# CONNECTORS.net
KiCad netlist of a schematic drawn in Altium Designer
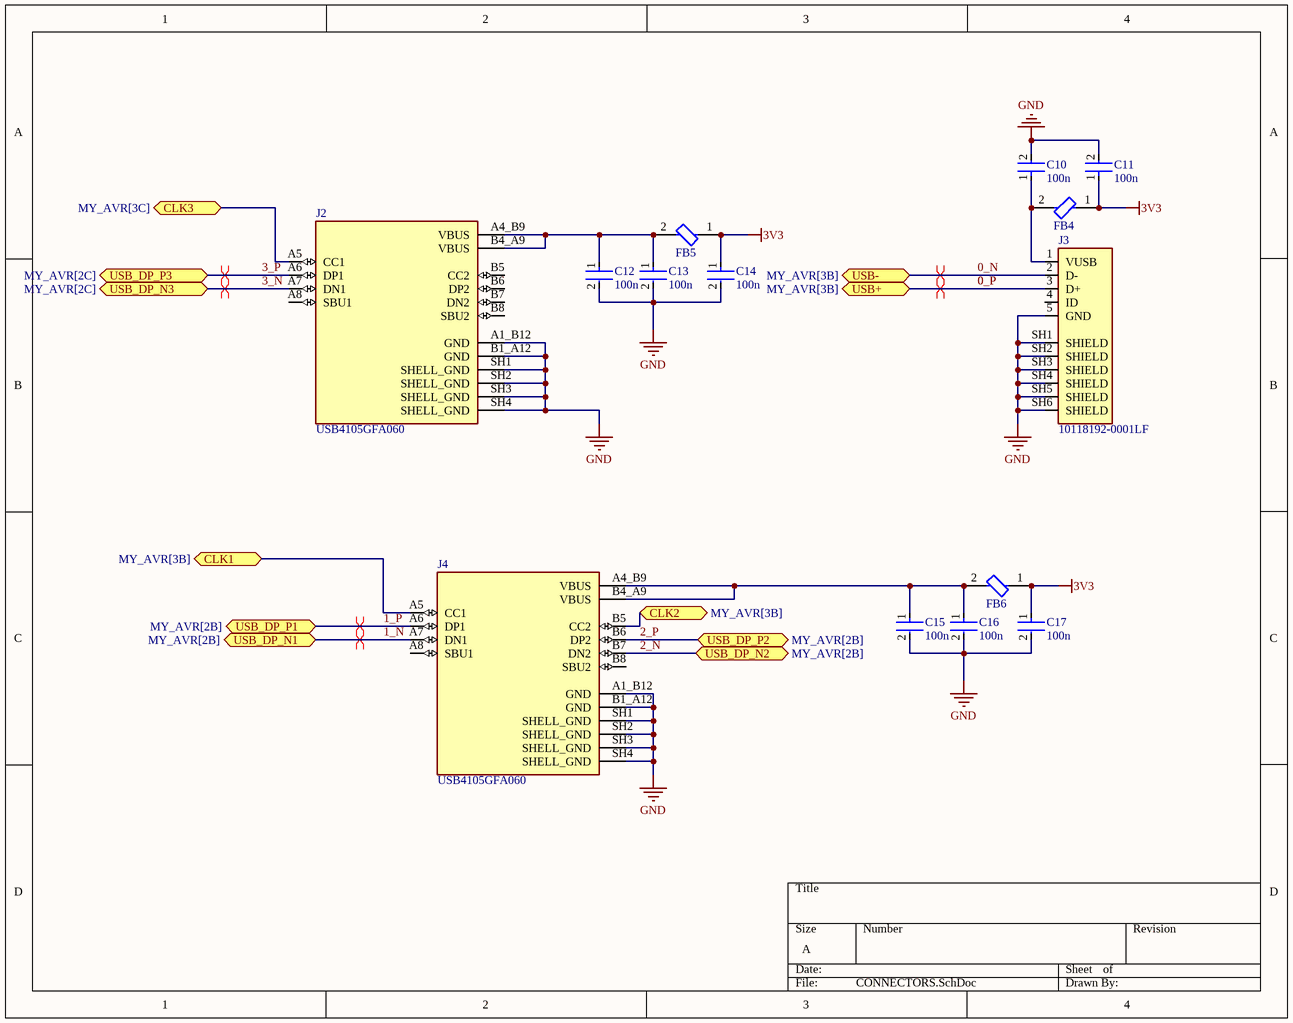
[diagram p0: CONNECTORS.SchDoc]

(export (version "E")
  (design (tool "Eeschema 10.0.6"))
  (components
    (comp (ref "C10")
      (value "100n")
      (footprint "FP-CL10-IPC_C")
      (description "Cap Ceramic 4.7uF 10V X5R ±10% Pad SMD 0603 +85°C T/R")
      (fields (field (name "TOLERANCE") "10%"))
      (libsource (lib "Altium Content Vault") (part "b4654b650e69147ec39a6b967a45e02"))
    )
    (comp (ref "C11")
      (value "100n")
      (footprint "FP-CL10-IPC_C")
      (description "Cap Ceramic 4.7uF 10V X5R ±10% Pad SMD 0603 +85°C T/R")
      (fields (field (name "TOLERANCE") "10%"))
      (libsource (lib "Altium Content Vault") (part "b4654b650e69147ec39a6b967a45e02"))
    )
    (comp (ref "C12")
      (value "100n")
      (footprint "FP-CL10-IPC_C")
      (description "Cap Ceramic 4.7uF 10V X5R ±10% Pad SMD 0603 +85°C T/R")
      (fields (field (name "TOLERANCE") "10%"))
      (libsource (lib "Altium Content Vault") (part "b4654b650e69147ec39a6b967a45e02"))
    )
    (comp (ref "C13")
      (value "100n")
      (footprint "FP-CL10-IPC_C")
      (description "Cap Ceramic 4.7uF 10V X5R ±10% Pad SMD 0603 +85°C T/R")
      (fields (field (name "TOLERANCE") "10%"))
      (libsource (lib "Altium Content Vault") (part "b4654b650e69147ec39a6b967a45e02"))
    )
    (comp (ref "C14")
      (value "100n")
      (footprint "FP-CL10-IPC_C")
      (description "Cap Ceramic 4.7uF 10V X5R ±10% Pad SMD 0603 +85°C T/R")
      (fields (field (name "TOLERANCE") "10%"))
      (libsource (lib "Altium Content Vault") (part "b4654b650e69147ec39a6b967a45e02"))
    )
    (comp (ref "C15")
      (value "100n")
      (footprint "FP-CL10-IPC_C")
      (description "Cap Ceramic 4.7uF 10V X5R ±10% Pad SMD 0603 +85°C T/R")
      (fields (field (name "TOLERANCE") "10%"))
      (libsource (lib "Altium Content Vault") (part "b4654b650e69147ec39a6b967a45e02"))
    )
    (comp (ref "C16")
      (value "100n")
      (footprint "FP-CL10-IPC_C")
      (description "Cap Ceramic 4.7uF 10V X5R ±10% Pad SMD 0603 +85°C T/R")
      (fields (field (name "TOLERANCE") "10%"))
      (libsource (lib "Altium Content Vault") (part "b4654b650e69147ec39a6b967a45e02"))
    )
    (comp (ref "C17")
      (value "100n")
      (footprint "FP-CL10-IPC_C")
      (description "Cap Ceramic 4.7uF 10V X5R ±10% Pad SMD 0603 +85°C T/R")
      (fields (field (name "TOLERANCE") "10%"))
      (libsource (lib "Altium Content Vault") (part "b4654b650e69147ec39a6b967a45e02"))
    )
    (comp (ref "FB4")
      (value "BLM18KG121TN1D")
      (footprint "FP-BLM18-0_15-t0_6-d1_2-IPC_A")
      (description "FERRITE BEAD 120 OHM 0603 1LN")
      (fields (field (name "TOLERANCE") "25%"))
      (libsource (lib "Altium Content Vault") (part "5f30dd21d616792df468990f7003faa"))
    )
    (comp (ref "FB5")
      (value "BLM18KG121TN1D")
      (footprint "FP-BLM18-0_15-t0_6-d1_2-IPC_A")
      (description "FERRITE BEAD 120 OHM 0603 1LN")
      (fields (field (name "TOLERANCE") "25%"))
      (libsource (lib "Altium Content Vault") (part "5f30dd21d616792df468990f7003faa"))
    )
    (comp (ref "FB6")
      (value "BLM18KG121TN1D")
      (footprint "FP-BLM18-0_15-t0_6-d1_2-IPC_A")
      (description "FERRITE BEAD 120 OHM 0603 1LN")
      (fields (field (name "TOLERANCE") "25%"))
      (libsource (lib "Altium Content Vault") (part "5f30dd21d616792df468990f7003faa"))
    )
    (comp (ref "J2")
      (value "USB4105GFA060")
      (footprint "GCT_USB4105GFA060")
      (fields (field (name "MF") "{'manufacturer': u'GCT'}"))
      (libsource (lib "USB4105GFA060") (part "USB4105GFA060"))
    )
    (comp (ref "J3")
      (value "10118192-0001LF")
      (footprint "AMPHENOL_10118192-0001LF")
      (description "Micro USB, Input Output Connectors, B TYPE RECEPTACLE with flange")
      (fields (field (name "MF") "Amphenol ICC"))
      (libsource (lib "10118192-0001LF") (part "10118192-0001LF"))
    )
    (comp (ref "J4")
      (value "USB4105GFA060")
      (footprint "GCT_USB4105GFA060")
      (fields (field (name "MF") "{'manufacturer': u'GCT'}"))
      (libsource (lib "USB4105GFA060") (part "USB4105GFA060"))
    )
  )
  (nets
    (net (code "1") (name "/0_N") (class "Default")
      (node (ref "J3") (pin "2") (pinfunction "D-_2") (pintype "passive"))
    )
    (net (code "2") (name "/0_P") (class "Default")
      (node (ref "J3") (pin "3") (pinfunction "D+_3") (pintype "passive"))
    )
    (net (code "3") (name "/1_N") (class "Default")
      (node (ref "J4") (pin "A7") (pinfunction "DN1_A7") (pintype "bidirectional"))
    )
    (net (code "4") (name "/1_P") (class "Default")
      (node (ref "J4") (pin "A6") (pinfunction "DP1_A6") (pintype "bidirectional"))
    )
    (net (code "5") (name "/2_N") (class "Default")
      (node (ref "J4") (pin "B7") (pinfunction "DN2_B7") (pintype "bidirectional"))
    )
    (net (code "6") (name "/2_P") (class "Default")
      (node (ref "J4") (pin "B6") (pinfunction "DP2_B6") (pintype "bidirectional"))
    )
    (net (code "7") (name "/3_N") (class "Default")
      (node (ref "J2") (pin "A7") (pinfunction "DN1_A7") (pintype "bidirectional"))
    )
    (net (code "8") (name "/3_P") (class "Default")
      (node (ref "J2") (pin "A6") (pinfunction "DP1_A6") (pintype "bidirectional"))
    )
    (net (code "9") (name "/CLK1") (class "Default")
      (node (ref "J4") (pin "A5") (pinfunction "CC1_A5") (pintype "bidirectional"))
    )
    (net (code "10") (name "/CLK2") (class "Default")
      (node (ref "J4") (pin "B5") (pinfunction "CC2_B5") (pintype "bidirectional"))
    )
    (net (code "11") (name "/CLK3") (class "Default")
      (node (ref "J2") (pin "A5") (pinfunction "CC1_A5") (pintype "bidirectional"))
    )
    (net (code "12") (name "3V3") (class "Default")
      (node (ref "C11") (pin "1") (pinfunction "1_1") (pintype "passive"))
      (node (ref "C14") (pin "1") (pinfunction "1_1") (pintype "passive"))
      (node (ref "C17") (pin "1") (pinfunction "1_1") (pintype "passive"))
      (node (ref "FB4") (pin "1") (pinfunction "1_1") (pintype "passive"))
      (node (ref "FB5") (pin "1") (pinfunction "1_1") (pintype "passive"))
      (node (ref "FB6") (pin "1") (pinfunction "1_1") (pintype "passive"))
    )
    (net (code "13") (name "GND") (class "Default")
      (node (ref "C10") (pin "2") (pinfunction "2_2") (pintype "passive"))
      (node (ref "C11") (pin "2") (pinfunction "2_2") (pintype "passive"))
      (node (ref "C12") (pin "2") (pinfunction "2_2") (pintype "passive"))
      (node (ref "C13") (pin "2") (pinfunction "2_2") (pintype "passive"))
      (node (ref "C14") (pin "2") (pinfunction "2_2") (pintype "passive"))
      (node (ref "C15") (pin "2") (pinfunction "2_2") (pintype "passive"))
      (node (ref "C16") (pin "2") (pinfunction "2_2") (pintype "passive"))
      (node (ref "C17") (pin "2") (pinfunction "2_2") (pintype "passive"))
      (node (ref "J2") (pin "A1_B12") (pinfunction "GND_A1_B12") (pintype "power_in"))
      (node (ref "J2") (pin "B1_A12") (pinfunction "GND_B1_A12") (pintype "power_in"))
      (node (ref "J2") (pin "SH1") (pinfunction "SHELL_GND_SH1") (pintype "power_in"))
      (node (ref "J2") (pin "SH2") (pinfunction "SHELL_GND_SH2") (pintype "power_in"))
      (node (ref "J2") (pin "SH3") (pinfunction "SHELL_GND_SH3") (pintype "power_in"))
      (node (ref "J2") (pin "SH4") (pinfunction "SHELL_GND_SH4") (pintype "power_in"))
      (node (ref "J3") (pin "5") (pinfunction "GND_5") (pintype "passive"))
      (node (ref "J3") (pin "SH1") (pinfunction "SHIELD_SH1") (pintype "passive"))
      (node (ref "J3") (pin "SH2") (pinfunction "SHIELD_SH2") (pintype "passive"))
      (node (ref "J3") (pin "SH3") (pinfunction "SHIELD_SH3") (pintype "passive"))
      (node (ref "J3") (pin "SH4") (pinfunction "SHIELD_SH4") (pintype "passive"))
      (node (ref "J3") (pin "SH5") (pinfunction "SHIELD_SH5") (pintype "passive"))
      (node (ref "J3") (pin "SH6") (pinfunction "SHIELD_SH6") (pintype "passive"))
      (node (ref "J4") (pin "A1_B12") (pinfunction "GND_A1_B12") (pintype "power_in"))
      (node (ref "J4") (pin "B1_A12") (pinfunction "GND_B1_A12") (pintype "power_in"))
      (node (ref "J4") (pin "SH1") (pinfunction "SHELL_GND_SH1") (pintype "power_in"))
      (node (ref "J4") (pin "SH2") (pinfunction "SHELL_GND_SH2") (pintype "power_in"))
      (node (ref "J4") (pin "SH3") (pinfunction "SHELL_GND_SH3") (pintype "power_in"))
      (node (ref "J4") (pin "SH4") (pinfunction "SHELL_GND_SH4") (pintype "power_in"))
    )
    (net (code "14") (name "Net-(C12-Pad1)") (class "Default")
      (node (ref "C12") (pin "1") (pinfunction "1_1") (pintype "passive"))
      (node (ref "C13") (pin "1") (pinfunction "1_1") (pintype "passive"))
      (node (ref "FB5") (pin "2") (pinfunction "2_2") (pintype "passive"))
      (node (ref "J2") (pin "A4_B9") (pinfunction "VBUS_A4_B9") (pintype "power_in"))
      (node (ref "J2") (pin "B4_A9") (pinfunction "VBUS_B4_A9") (pintype "power_in"))
    )
    (net (code "15") (name "Net-(C15-Pad1)") (class "Default")
      (node (ref "C15") (pin "1") (pinfunction "1_1") (pintype "passive"))
      (node (ref "C16") (pin "1") (pinfunction "1_1") (pintype "passive"))
      (node (ref "FB6") (pin "2") (pinfunction "2_2") (pintype "passive"))
      (node (ref "J4") (pin "A4_B9") (pinfunction "VBUS_A4_B9") (pintype "power_in"))
      (node (ref "J4") (pin "B4_A9") (pinfunction "VBUS_B4_A9") (pintype "power_in"))
    )
    (net (code "16") (name "Net-(J3-VUSB)") (class "Default")
      (node (ref "C10") (pin "1") (pinfunction "1_1") (pintype "passive"))
      (node (ref "FB4") (pin "2") (pinfunction "2_2") (pintype "passive"))
      (node (ref "J3") (pin "1") (pinfunction "VUSB_1") (pintype "passive"))
    )
    (net (code "17") (name "unconnected-(J2-CC2-PadB5)") (class "Default")
      (node (ref "J2") (pin "B5") (pinfunction "CC2_B5") (pintype "bidirectional"))
    )
    (net (code "18") (name "unconnected-(J2-DN2-PadB7)") (class "Default")
      (node (ref "J2") (pin "B7") (pinfunction "DN2_B7") (pintype "bidirectional"))
    )
    (net (code "19") (name "unconnected-(J2-DP2-PadB6)") (class "Default")
      (node (ref "J2") (pin "B6") (pinfunction "DP2_B6") (pintype "bidirectional"))
    )
    (net (code "20") (name "unconnected-(J2-SBU1-PadA8)") (class "Default")
      (node (ref "J2") (pin "A8") (pinfunction "SBU1_A8") (pintype "bidirectional"))
    )
    (net (code "21") (name "unconnected-(J2-SBU2-PadB8)") (class "Default")
      (node (ref "J2") (pin "B8") (pinfunction "SBU2_B8") (pintype "bidirectional"))
    )
    (net (code "22") (name "unconnected-(J3-ID-Pad4)") (class "Default")
      (node (ref "J3") (pin "4") (pinfunction "ID_4") (pintype "passive"))
    )
    (net (code "23") (name "unconnected-(J4-SBU1-PadA8)") (class "Default")
      (node (ref "J4") (pin "A8") (pinfunction "SBU1_A8") (pintype "bidirectional"))
    )
    (net (code "24") (name "unconnected-(J4-SBU2-PadB8)") (class "Default")
      (node (ref "J4") (pin "B8") (pinfunction "SBU2_B8") (pintype "bidirectional"))
    )
  )
)
